# single_sensor.net
KiCad netlist of a schematic drawn in EAGLE
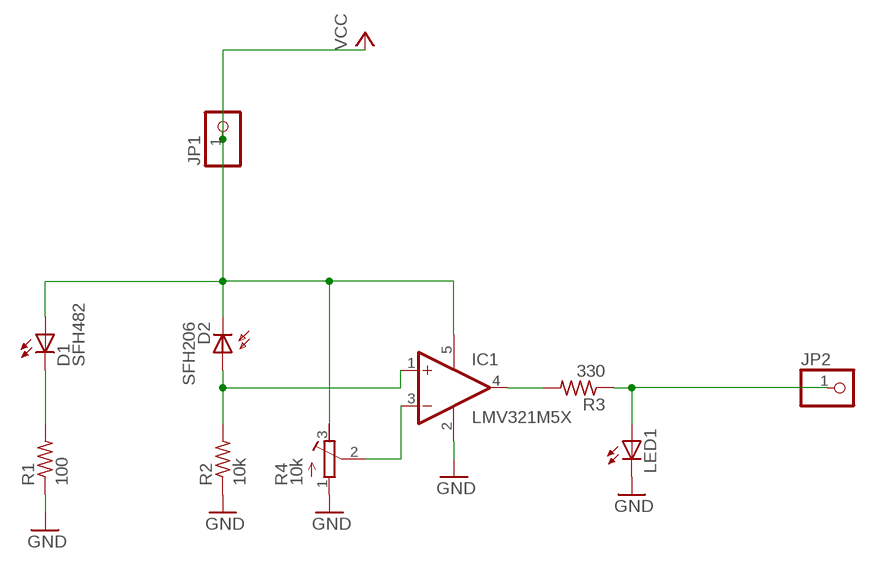
[diagram p0: schematic, sheet 1]

(export (version "E")
  (design (tool "Eeschema 10.0.6"))
  (components
    (comp (ref "D1")
      (value "SFH482")
      (footprint "eagle-import:SFH482")
      (libsource (lib "eagle-import") (part "SFH482"))
    )
    (comp (ref "D2")
      (value "SFH206")
      (footprint "eagle-import:SFH206")
      (fields (field (name "MPN") "SFH206K"))
      (libsource (lib "eagle-import") (part "SFH206"))
    )
    (comp (ref "IC1")
      (value "LMV321M5X")
      (footprint "eagle-import:SOT23-5")
      (libsource (lib "eagle-import") (part "LMV321?M5X"))
    )
    (comp (ref "JP1")
      (value "PINHD-1X1")
      (footprint "eagle-import:1X01")
      (libsource (lib "eagle-import") (part "PINHD-1X1"))
    )
    (comp (ref "JP2")
      (value "PINHD-1X1")
      (footprint "eagle-import:1X01")
      (libsource (lib "eagle-import") (part "PINHD-1X1"))
    )
    (comp (ref "LED1")
      (value "LED5MM")
      (footprint "eagle-import:LED5MM")
      (libsource (lib "eagle-import") (part "LED5MM"))
    )
    (comp (ref "R1")
      (value "100")
      (footprint "eagle-import:0207_7")
      (libsource (lib "eagle-import") (part "R-US_0207/7"))
    )
    (comp (ref "R2")
      (value "10k")
      (footprint "eagle-import:0207_7")
      (libsource (lib "eagle-import") (part "R-US_0207/7"))
    )
    (comp (ref "R3")
      (value "330")
      (footprint "eagle-import:0207_7")
      (libsource (lib "eagle-import") (part "R-US_0207/7"))
    )
    (comp (ref "R4")
      (value "10k")
      (footprint "eagle-import:RTRIM5X")
      (libsource (lib "eagle-import") (part "R-TRIMM5X"))
    )
  )
  (nets
    (net (code "1") (name "GND") (class "Default")
      (node (ref "IC1") (pin "2") (pinfunction "V-_2") (pintype "power_in"))
      (node (ref "LED1") (pin "K") (pinfunction "C_K") (pintype "passive"))
      (node (ref "R1") (pin "1") (pinfunction "1_1") (pintype "passive"))
      (node (ref "R2") (pin "1") (pinfunction "1_1") (pintype "passive"))
      (node (ref "R4") (pin "1") (pinfunction "A_1") (pintype "passive"))
    )
    (net (code "2") (name "Net-(D1-C)") (class "Default")
      (node (ref "D1") (pin "K") (pinfunction "C_K") (pintype "passive"))
      (node (ref "R1") (pin "2") (pinfunction "2_2") (pintype "passive"))
    )
    (net (code "3") (name "Net-(IC1-+IN)") (class "Default")
      (node (ref "D2") (pin "A") (pinfunction "A_A") (pintype "passive"))
      (node (ref "IC1") (pin "1") (pinfunction "+IN_1") (pintype "input"))
      (node (ref "R2") (pin "2") (pinfunction "2_2") (pintype "passive"))
    )
    (net (code "4") (name "Net-(IC1--IN)") (class "Default")
      (node (ref "IC1") (pin "3") (pinfunction "-IN_3") (pintype "input"))
      (node (ref "R4") (pin "2") (pinfunction "S_2") (pintype "passive"))
    )
    (net (code "5") (name "Net-(IC1-OUT)") (class "Default")
      (node (ref "IC1") (pin "4") (pinfunction "OUT_4") (pintype "output"))
      (node (ref "R3") (pin "2") (pinfunction "2_2") (pintype "passive"))
    )
    (net (code "6") (name "Net-(JP2-Pad1)") (class "Default")
      (node (ref "JP2") (pin "1") (pinfunction "1_1") (pintype "passive"))
      (node (ref "LED1") (pin "A") (pinfunction "A_A") (pintype "passive"))
      (node (ref "R3") (pin "1") (pinfunction "1_1") (pintype "passive"))
    )
    (net (code "7") (name "VCC") (class "Default")
      (node (ref "D1") (pin "A") (pinfunction "A_A") (pintype "passive"))
      (node (ref "D2") (pin "K") (pinfunction "C_K") (pintype "passive"))
      (node (ref "IC1") (pin "5") (pinfunction "V+_5") (pintype "power_in"))
      (node (ref "JP1") (pin "1") (pinfunction "1_1") (pintype "passive"))
      (node (ref "R4") (pin "3") (pinfunction "E_3") (pintype "passive"))
    )
  )
)
